# hycomBridge_Beginner_V6.net
KiCad netlist of a schematic drawn in EAGLE
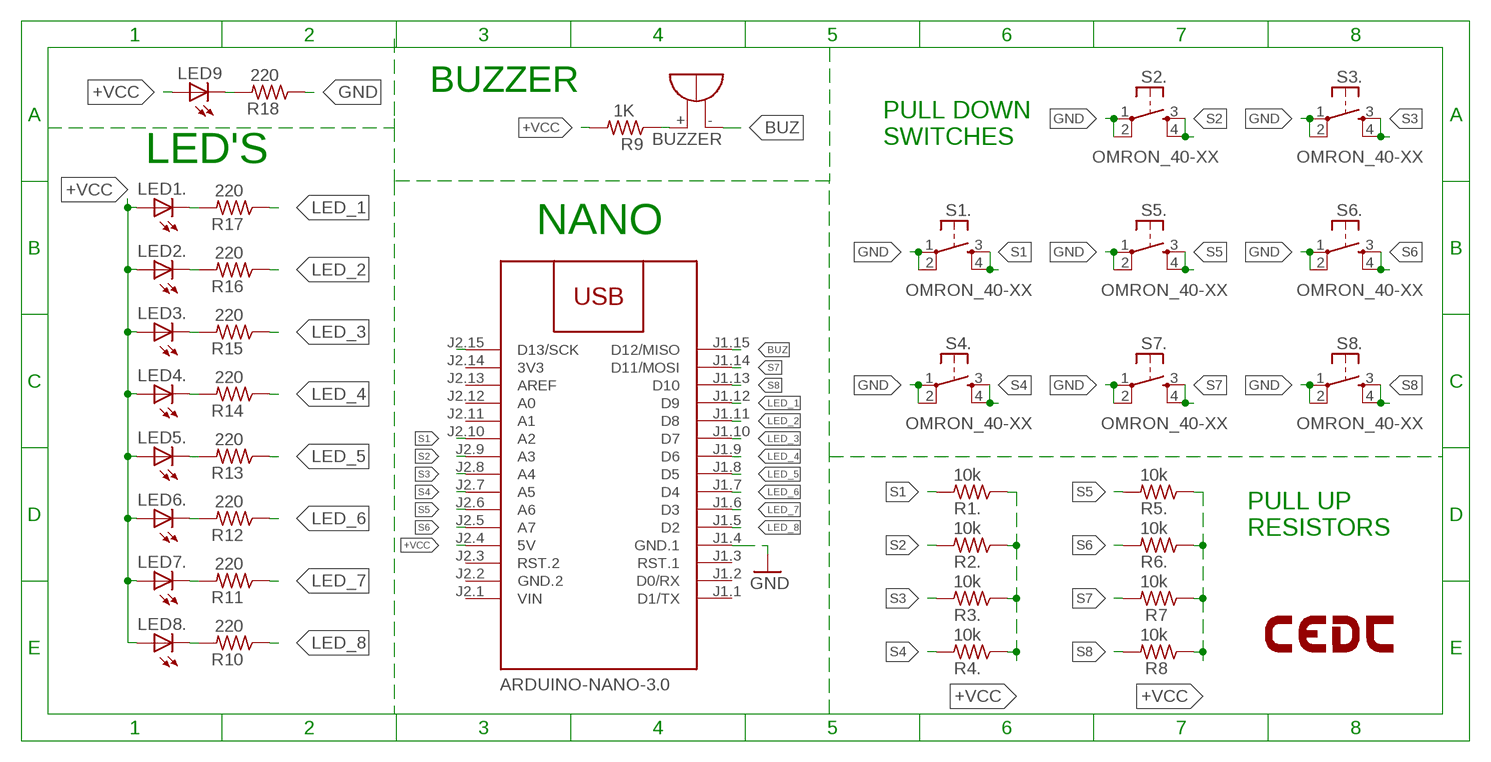
[diagram p0: schematic, sheet 1]

(export (version "E")
  (design (tool "Eeschema 10.0.6"))
  (components
    (comp (ref "ARDUINO_NANO")
      (value "ARDUINO-NANO-3.0")
      (footprint "eagle-import:ARDUINO-NANO-3.0")
      (libsource (lib "eagle-import") (part "ARDUINO-NANO-3.0"))
    )
    (comp (ref "LED1.")
      (value "LED5MM")
      (footprint "eagle-import:LED5MM")
      (libsource (lib "eagle-import") (part "LED5MM"))
    )
    (comp (ref "LED2.")
      (value "LED5MM")
      (footprint "eagle-import:LED5MM")
      (libsource (lib "eagle-import") (part "LED5MM"))
    )
    (comp (ref "LED3.")
      (value "LED5MM")
      (footprint "eagle-import:LED5MM")
      (libsource (lib "eagle-import") (part "LED5MM"))
    )
    (comp (ref "LED4.")
      (value "LED5MM")
      (footprint "eagle-import:LED5MM")
      (libsource (lib "eagle-import") (part "LED5MM"))
    )
    (comp (ref "LED5.")
      (value "LED5MM")
      (footprint "eagle-import:LED5MM")
      (libsource (lib "eagle-import") (part "LED5MM"))
    )
    (comp (ref "LED6.")
      (value "LED5MM")
      (footprint "eagle-import:LED5MM")
      (libsource (lib "eagle-import") (part "LED5MM"))
    )
    (comp (ref "LED7.")
      (value "LED5MM")
      (footprint "eagle-import:LED5MM")
      (libsource (lib "eagle-import") (part "LED5MM"))
    )
    (comp (ref "LED8.")
      (value "LED5MM")
      (footprint "eagle-import:LED5MM")
      (libsource (lib "eagle-import") (part "LED5MM"))
    )
    (comp (ref "LED9")
      (value "LED3MM")
      (footprint "eagle-import:LED3MM")
      (libsource (lib "eagle-import") (part "adafruit_420_LED3MM"))
    )
    (comp (ref "LOGO1")
      (value "LOGO-CEDTBOT-18MM")
      (footprint "eagle-import:LOGO-CEDT-BOT-18MM")
      (libsource (lib "eagle-import") (part "LOGO-CEDTBOT-18MM"))
    )
    (comp (ref "LOGO2")
      (value "LOGO-CEDTSILK-18MM")
      (footprint "eagle-import:LOGO-CEDT-SILK-18MM")
      (libsource (lib "eagle-import") (part "LOGO-CEDTSILK-18MM"))
    )
    (comp (ref "R1.")
      (value "10k")
      (footprint "eagle-import:0207_10")
      (libsource (lib "eagle-import") (part "RESISTOR0207/10"))
    )
    (comp (ref "R2.")
      (value "10k")
      (footprint "eagle-import:0207_10")
      (libsource (lib "eagle-import") (part "RESISTOR0207/10"))
    )
    (comp (ref "R3.")
      (value "10k")
      (footprint "eagle-import:0207_10")
      (libsource (lib "eagle-import") (part "RESISTOR0207/10"))
    )
    (comp (ref "R4.")
      (value "10k")
      (footprint "eagle-import:0207_10")
      (libsource (lib "eagle-import") (part "RESISTOR0207/10"))
    )
    (comp (ref "R5.")
      (value "10k")
      (footprint "eagle-import:0207_10")
      (libsource (lib "eagle-import") (part "RESISTOR0207/10"))
    )
    (comp (ref "R6.")
      (value "10k")
      (footprint "eagle-import:0207_10")
      (libsource (lib "eagle-import") (part "RESISTOR0207/10"))
    )
    (comp (ref "R7")
      (value "10k")
      (footprint "eagle-import:0207_10")
      (libsource (lib "eagle-import") (part "RESISTOR0207/10"))
    )
    (comp (ref "R8")
      (value "10k")
      (footprint "eagle-import:0207_10")
      (libsource (lib "eagle-import") (part "RESISTOR0207/10"))
    )
    (comp (ref "R9")
      (value "1K")
      (footprint "eagle-import:0207_10")
      (libsource (lib "eagle-import") (part "RESISTOR0207/10"))
    )
    (comp (ref "R10")
      (value "220")
      (footprint "eagle-import:0207_10")
      (libsource (lib "eagle-import") (part "RESISTOR0207/10"))
    )
    (comp (ref "R11")
      (value "220")
      (footprint "eagle-import:0207_10")
      (libsource (lib "eagle-import") (part "RESISTOR0207/10"))
    )
    (comp (ref "R12")
      (value "220")
      (footprint "eagle-import:0207_10")
      (libsource (lib "eagle-import") (part "RESISTOR0207/10"))
    )
    (comp (ref "R13")
      (value "220")
      (footprint "eagle-import:0207_10")
      (libsource (lib "eagle-import") (part "RESISTOR0207/10"))
    )
    (comp (ref "R14")
      (value "220")
      (footprint "eagle-import:0207_10")
      (libsource (lib "eagle-import") (part "RESISTOR0207/10"))
    )
    (comp (ref "R15")
      (value "220")
      (footprint "eagle-import:0207_10")
      (libsource (lib "eagle-import") (part "RESISTOR0207/10"))
    )
    (comp (ref "R16")
      (value "220")
      (footprint "eagle-import:0207_10")
      (libsource (lib "eagle-import") (part "RESISTOR0207/10"))
    )
    (comp (ref "R17")
      (value "220")
      (footprint "eagle-import:0207_10")
      (libsource (lib "eagle-import") (part "RESISTOR0207/10"))
    )
    (comp (ref "R18")
      (value "220")
      (footprint "eagle-import:0207_10")
      (libsource (lib "eagle-import") (part "RESISTOR0207/10"))
    )
    (comp (ref "S1.")
      (value "OMRON_40-XX")
      (footprint "eagle-import:B3F-40XX")
      (libsource (lib "eagle-import") (part "OMRON_SWITCH_40-XX"))
    )
    (comp (ref "S2.")
      (value "OMRON_40-XX")
      (footprint "eagle-import:B3F-40XX")
      (libsource (lib "eagle-import") (part "OMRON_SWITCH_40-XX"))
    )
    (comp (ref "S3.")
      (value "OMRON_40-XX")
      (footprint "eagle-import:B3F-40XX")
      (libsource (lib "eagle-import") (part "OMRON_SWITCH_40-XX"))
    )
    (comp (ref "S4.")
      (value "OMRON_40-XX")
      (footprint "eagle-import:B3F-40XX")
      (libsource (lib "eagle-import") (part "OMRON_SWITCH_40-XX"))
    )
    (comp (ref "S5.")
      (value "OMRON_40-XX")
      (footprint "eagle-import:B3F-40XX")
      (libsource (lib "eagle-import") (part "OMRON_SWITCH_40-XX"))
    )
    (comp (ref "S6.")
      (value "OMRON_40-XX")
      (footprint "eagle-import:B3F-40XX")
      (libsource (lib "eagle-import") (part "OMRON_SWITCH_40-XX"))
    )
    (comp (ref "S7.")
      (value "OMRON_40-XX")
      (footprint "eagle-import:B3F-40XX")
      (libsource (lib "eagle-import") (part "OMRON_SWITCH_40-XX"))
    )
    (comp (ref "S8.")
      (value "OMRON_40-XX")
      (footprint "eagle-import:B3F-40XX")
      (libsource (lib "eagle-import") (part "OMRON_SWITCH_40-XX"))
    )
    (comp (ref "SG1")
      (value "BUZZER")
      (footprint "eagle-import:F_TMB")
      (libsource (lib "eagle-import") (part "BUZZER"))
    )
  )
  (nets
    (net (code "1") (name "+VCC") (class "Default")
      (node (ref "ARDUINO_NANO") (pin "J2.4") (pinfunction "5V_J2.4") (pintype "power_in"))
      (node (ref "LED1.") (pin "A") (pinfunction "A_A") (pintype "passive"))
      (node (ref "LED2.") (pin "A") (pinfunction "A_A") (pintype "passive"))
      (node (ref "LED3.") (pin "A") (pinfunction "A_A") (pintype "passive"))
      (node (ref "LED4.") (pin "A") (pinfunction "A_A") (pintype "passive"))
      (node (ref "LED5.") (pin "A") (pinfunction "A_A") (pintype "passive"))
      (node (ref "LED6.") (pin "A") (pinfunction "A_A") (pintype "passive"))
      (node (ref "LED7.") (pin "A") (pinfunction "A_A") (pintype "passive"))
      (node (ref "LED8.") (pin "A") (pinfunction "A_A") (pintype "passive"))
      (node (ref "LED9") (pin "A") (pinfunction "A_A") (pintype "passive"))
      (node (ref "R1.") (pin "1") (pinfunction "1_1") (pintype "passive"))
      (node (ref "R2.") (pin "1") (pinfunction "1_1") (pintype "passive"))
      (node (ref "R3.") (pin "1") (pinfunction "1_1") (pintype "passive"))
      (node (ref "R4.") (pin "1") (pinfunction "1_1") (pintype "passive"))
      (node (ref "R5.") (pin "1") (pinfunction "1_1") (pintype "passive"))
      (node (ref "R6.") (pin "1") (pinfunction "1_1") (pintype "passive"))
      (node (ref "R7") (pin "1") (pinfunction "1_1") (pintype "passive"))
      (node (ref "R8") (pin "1") (pinfunction "1_1") (pintype "passive"))
      (node (ref "R9") (pin "2") (pinfunction "2_2") (pintype "passive"))
    )
    (net (code "2") (name "/3V3") (class "Default")
      (node (ref "ARDUINO_NANO") (pin "J2.14") (pinfunction "3V3_J2.14") (pintype "power_in"))
    )
    (net (code "3") (name "/GND.2") (class "Default")
      (node (ref "ARDUINO_NANO") (pin "J2.2") (pinfunction "GND.2_J2.2") (pintype "power_in"))
    )
    (net (code "4") (name "/VIN") (class "Default")
      (node (ref "ARDUINO_NANO") (pin "J2.1") (pinfunction "VIN_J2.1") (pintype "power_in"))
    )
    (net (code "5") (name "BUZ") (class "Default")
      (node (ref "ARDUINO_NANO") (pin "J1.15") (pinfunction "D12/MISO_J1.15") (pintype "bidirectional"))
      (node (ref "SG1") (pin "-") (pinfunction "-_-") (pintype "passive"))
    )
    (net (code "6") (name "GND") (class "Default")
      (node (ref "ARDUINO_NANO") (pin "J1.4") (pinfunction "GND.1_J1.4") (pintype "power_in"))
      (node (ref "R18") (pin "1") (pinfunction "1_1") (pintype "passive"))
      (node (ref "S1.") (pin "1") (pinfunction "P_1") (pintype "passive"))
      (node (ref "S1.") (pin "2") (pinfunction "P1_2") (pintype "passive"))
      (node (ref "S2.") (pin "1") (pinfunction "P_1") (pintype "passive"))
      (node (ref "S2.") (pin "2") (pinfunction "P1_2") (pintype "passive"))
      (node (ref "S3.") (pin "1") (pinfunction "P_1") (pintype "passive"))
      (node (ref "S3.") (pin "2") (pinfunction "P1_2") (pintype "passive"))
      (node (ref "S4.") (pin "1") (pinfunction "P_1") (pintype "passive"))
      (node (ref "S4.") (pin "2") (pinfunction "P1_2") (pintype "passive"))
      (node (ref "S5.") (pin "1") (pinfunction "P_1") (pintype "passive"))
      (node (ref "S5.") (pin "2") (pinfunction "P1_2") (pintype "passive"))
      (node (ref "S6.") (pin "1") (pinfunction "P_1") (pintype "passive"))
      (node (ref "S6.") (pin "2") (pinfunction "P1_2") (pintype "passive"))
      (node (ref "S7.") (pin "1") (pinfunction "P_1") (pintype "passive"))
      (node (ref "S7.") (pin "2") (pinfunction "P1_2") (pintype "passive"))
      (node (ref "S8.") (pin "1") (pinfunction "P_1") (pintype "passive"))
      (node (ref "S8.") (pin "2") (pinfunction "P1_2") (pintype "passive"))
    )
    (net (code "7") (name "LED_1") (class "Default")
      (node (ref "ARDUINO_NANO") (pin "J1.12") (pinfunction "D9_J1.12") (pintype "bidirectional"))
      (node (ref "R17") (pin "1") (pinfunction "1_1") (pintype "passive"))
    )
    (net (code "8") (name "LED_2") (class "Default")
      (node (ref "ARDUINO_NANO") (pin "J1.11") (pinfunction "D8_J1.11") (pintype "bidirectional"))
      (node (ref "R16") (pin "1") (pinfunction "1_1") (pintype "passive"))
    )
    (net (code "9") (name "LED_3") (class "Default")
      (node (ref "ARDUINO_NANO") (pin "J1.10") (pinfunction "D7_J1.10") (pintype "bidirectional"))
      (node (ref "R15") (pin "1") (pinfunction "1_1") (pintype "passive"))
    )
    (net (code "10") (name "LED_4") (class "Default")
      (node (ref "ARDUINO_NANO") (pin "J1.9") (pinfunction "D6_J1.9") (pintype "bidirectional"))
      (node (ref "R14") (pin "1") (pinfunction "1_1") (pintype "passive"))
    )
    (net (code "11") (name "LED_5") (class "Default")
      (node (ref "ARDUINO_NANO") (pin "J1.8") (pinfunction "D5_J1.8") (pintype "bidirectional"))
      (node (ref "R13") (pin "1") (pinfunction "1_1") (pintype "passive"))
    )
    (net (code "12") (name "LED_6") (class "Default")
      (node (ref "ARDUINO_NANO") (pin "J1.7") (pinfunction "D4_J1.7") (pintype "bidirectional"))
      (node (ref "R12") (pin "1") (pinfunction "1_1") (pintype "passive"))
    )
    (net (code "13") (name "LED_7") (class "Default")
      (node (ref "ARDUINO_NANO") (pin "J1.6") (pinfunction "D3_J1.6") (pintype "bidirectional"))
      (node (ref "R11") (pin "1") (pinfunction "1_1") (pintype "passive"))
    )
    (net (code "14") (name "LED_8") (class "Default")
      (node (ref "ARDUINO_NANO") (pin "J1.5") (pinfunction "D2_J1.5") (pintype "bidirectional"))
      (node (ref "R10") (pin "1") (pinfunction "1_1") (pintype "passive"))
    )
    (net (code "15") (name "Net-(LED1.-C)") (class "Default")
      (node (ref "LED1.") (pin "K") (pinfunction "C_K") (pintype "passive"))
      (node (ref "R17") (pin "2") (pinfunction "2_2") (pintype "passive"))
    )
    (net (code "16") (name "Net-(LED2.-C)") (class "Default")
      (node (ref "LED2.") (pin "K") (pinfunction "C_K") (pintype "passive"))
      (node (ref "R16") (pin "2") (pinfunction "2_2") (pintype "passive"))
    )
    (net (code "17") (name "Net-(LED3.-C)") (class "Default")
      (node (ref "LED3.") (pin "K") (pinfunction "C_K") (pintype "passive"))
      (node (ref "R15") (pin "2") (pinfunction "2_2") (pintype "passive"))
    )
    (net (code "18") (name "Net-(LED4.-C)") (class "Default")
      (node (ref "LED4.") (pin "K") (pinfunction "C_K") (pintype "passive"))
      (node (ref "R14") (pin "2") (pinfunction "2_2") (pintype "passive"))
    )
    (net (code "19") (name "Net-(LED5.-C)") (class "Default")
      (node (ref "LED5.") (pin "K") (pinfunction "C_K") (pintype "passive"))
      (node (ref "R13") (pin "2") (pinfunction "2_2") (pintype "passive"))
    )
    (net (code "20") (name "Net-(LED6.-C)") (class "Default")
      (node (ref "LED6.") (pin "K") (pinfunction "C_K") (pintype "passive"))
      (node (ref "R12") (pin "2") (pinfunction "2_2") (pintype "passive"))
    )
    (net (code "21") (name "Net-(LED7.-C)") (class "Default")
      (node (ref "LED7.") (pin "K") (pinfunction "C_K") (pintype "passive"))
      (node (ref "R11") (pin "2") (pinfunction "2_2") (pintype "passive"))
    )
    (net (code "22") (name "Net-(LED8.-C)") (class "Default")
      (node (ref "LED8.") (pin "K") (pinfunction "C_K") (pintype "passive"))
      (node (ref "R10") (pin "2") (pinfunction "2_2") (pintype "passive"))
    )
    (net (code "23") (name "Net-(LED9-C)") (class "Default")
      (node (ref "LED9") (pin "K") (pinfunction "C_K") (pintype "passive"))
      (node (ref "R18") (pin "2") (pinfunction "2_2") (pintype "passive"))
    )
    (net (code "24") (name "Net-(R9-Pad1)") (class "Default")
      (node (ref "R9") (pin "1") (pinfunction "1_1") (pintype "passive"))
      (node (ref "SG1") (pin "+") (pinfunction "+_+") (pintype "passive"))
    )
    (net (code "25") (name "S1") (class "Default")
      (node (ref "ARDUINO_NANO") (pin "J2.10") (pinfunction "A2_J2.10") (pintype "bidirectional"))
      (node (ref "R1.") (pin "2") (pinfunction "2_2") (pintype "passive"))
      (node (ref "S1.") (pin "3") (pinfunction "S_3") (pintype "passive"))
      (node (ref "S1.") (pin "4") (pinfunction "S1_4") (pintype "passive"))
    )
    (net (code "26") (name "S2") (class "Default")
      (node (ref "ARDUINO_NANO") (pin "J2.9") (pinfunction "A3_J2.9") (pintype "bidirectional"))
      (node (ref "R2.") (pin "2") (pinfunction "2_2") (pintype "passive"))
      (node (ref "S2.") (pin "3") (pinfunction "S_3") (pintype "passive"))
      (node (ref "S2.") (pin "4") (pinfunction "S1_4") (pintype "passive"))
    )
    (net (code "27") (name "S3") (class "Default")
      (node (ref "ARDUINO_NANO") (pin "J2.8") (pinfunction "A4_J2.8") (pintype "bidirectional"))
      (node (ref "R3.") (pin "2") (pinfunction "2_2") (pintype "passive"))
      (node (ref "S3.") (pin "3") (pinfunction "S_3") (pintype "passive"))
      (node (ref "S3.") (pin "4") (pinfunction "S1_4") (pintype "passive"))
    )
    (net (code "28") (name "S4") (class "Default")
      (node (ref "ARDUINO_NANO") (pin "J2.7") (pinfunction "A5_J2.7") (pintype "bidirectional"))
      (node (ref "R4.") (pin "2") (pinfunction "2_2") (pintype "passive"))
      (node (ref "S4.") (pin "3") (pinfunction "S_3") (pintype "passive"))
      (node (ref "S4.") (pin "4") (pinfunction "S1_4") (pintype "passive"))
    )
    (net (code "29") (name "S5") (class "Default")
      (node (ref "ARDUINO_NANO") (pin "J2.6") (pinfunction "A6_J2.6") (pintype "bidirectional"))
      (node (ref "R5.") (pin "2") (pinfunction "2_2") (pintype "passive"))
      (node (ref "S5.") (pin "3") (pinfunction "S_3") (pintype "passive"))
      (node (ref "S5.") (pin "4") (pinfunction "S1_4") (pintype "passive"))
    )
    (net (code "30") (name "S6") (class "Default")
      (node (ref "ARDUINO_NANO") (pin "J2.5") (pinfunction "A7_J2.5") (pintype "bidirectional"))
      (node (ref "R6.") (pin "2") (pinfunction "2_2") (pintype "passive"))
      (node (ref "S6.") (pin "3") (pinfunction "S_3") (pintype "passive"))
      (node (ref "S6.") (pin "4") (pinfunction "S1_4") (pintype "passive"))
    )
    (net (code "31") (name "S7") (class "Default")
      (node (ref "ARDUINO_NANO") (pin "J1.14") (pinfunction "D11/MOSI_J1.14") (pintype "bidirectional"))
      (node (ref "R7") (pin "2") (pinfunction "2_2") (pintype "passive"))
      (node (ref "S7.") (pin "3") (pinfunction "S_3") (pintype "passive"))
      (node (ref "S7.") (pin "4") (pinfunction "S1_4") (pintype "passive"))
    )
    (net (code "32") (name "S8") (class "Default")
      (node (ref "ARDUINO_NANO") (pin "J1.13") (pinfunction "D10_J1.13") (pintype "bidirectional"))
      (node (ref "R8") (pin "2") (pinfunction "2_2") (pintype "passive"))
      (node (ref "S8.") (pin "3") (pinfunction "S_3") (pintype "passive"))
      (node (ref "S8.") (pin "4") (pinfunction "S1_4") (pintype "passive"))
    )
    (net (code "33") (name "unconnected-(ARDUINO_NANO-A0-PadJ2.12)") (class "Default")
      (node (ref "ARDUINO_NANO") (pin "J2.12") (pinfunction "A0_J2.12") (pintype "bidirectional"))
    )
    (net (code "34") (name "unconnected-(ARDUINO_NANO-A1-PadJ2.11)") (class "Default")
      (node (ref "ARDUINO_NANO") (pin "J2.11") (pinfunction "A1_J2.11") (pintype "bidirectional"))
    )
    (net (code "35") (name "unconnected-(ARDUINO_NANO-AREF-PadJ2.13)") (class "Default")
      (node (ref "ARDUINO_NANO") (pin "J2.13") (pinfunction "AREF_J2.13") (pintype "bidirectional"))
    )
    (net (code "36") (name "unconnected-(ARDUINO_NANO-D0{slash}RX-PadJ1.2)") (class "Default")
      (node (ref "ARDUINO_NANO") (pin "J1.2") (pinfunction "D0/RX_J1.2") (pintype "bidirectional"))
    )
    (net (code "37") (name "unconnected-(ARDUINO_NANO-D1{slash}TX-PadJ1.1)") (class "Default")
      (node (ref "ARDUINO_NANO") (pin "J1.1") (pinfunction "D1/TX_J1.1") (pintype "bidirectional"))
    )
    (net (code "38") (name "unconnected-(ARDUINO_NANO-D13{slash}SCK-PadJ2.15)") (class "Default")
      (node (ref "ARDUINO_NANO") (pin "J2.15") (pinfunction "D13/SCK_J2.15") (pintype "bidirectional"))
    )
    (net (code "39") (name "unconnected-(ARDUINO_NANO-RST.1-PadJ1.3)") (class "Default")
      (node (ref "ARDUINO_NANO") (pin "J1.3") (pinfunction "RST.1_J1.3") (pintype "bidirectional"))
    )
    (net (code "40") (name "unconnected-(ARDUINO_NANO-RST.2-PadJ2.3)") (class "Default")
      (node (ref "ARDUINO_NANO") (pin "J2.3") (pinfunction "RST.2_J2.3") (pintype "bidirectional"))
    )
  )
)
